# peripherals.net
KiCad netlist of a schematic drawn in Altium Designer
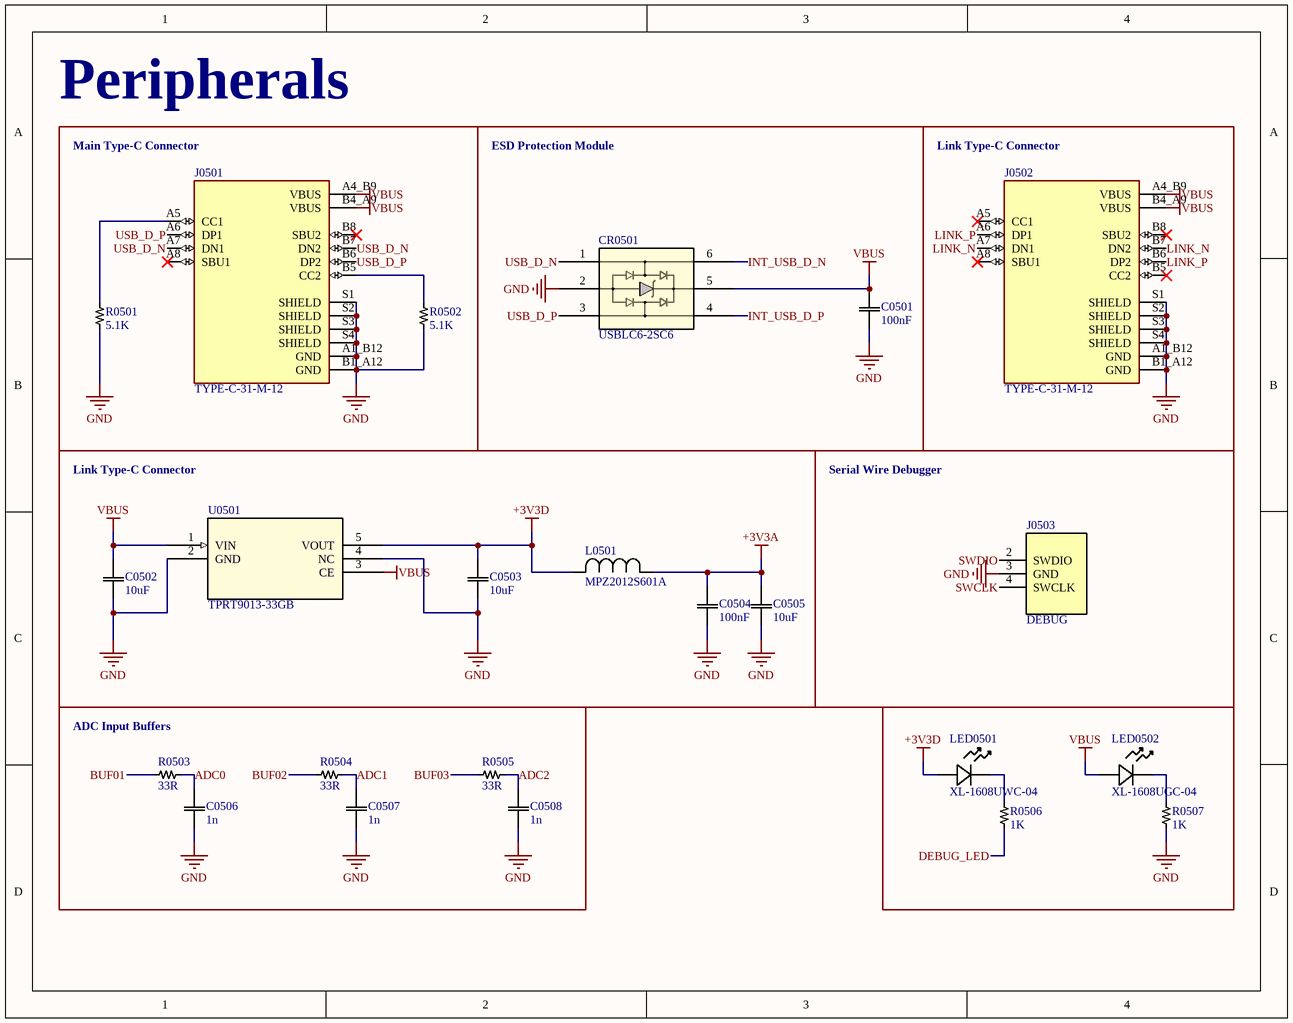
[diagram p0: peripherals.SchDoc]

(export (version "E")
  (design (tool "Eeschema 10.0.6"))
  (components
    (comp (ref "C0501")
      (value "100nF")
      (footprint "CAPC10555_55N_KEM")
      (description "SMD Comm X7R, Ceramic, SMD, MLCC, Temperature Stable, 0402")
      (fields
        (field (name "MANUFACTURER_PART_NUMBER") "C0402C104K4RACTU")
        (field (name "COPYRIGHT") "Copyright (C) 2025 Ultra Librarian. All rights reserved.")
      )
      (libsource (lib "SplitHE_Int") (part "C0402"))
    )
    (comp (ref "C0502")
      (value "10uF")
      (footprint "CAPC10555_55N_KEM")
      (description "SMD Comm X7R, Ceramic, SMD, MLCC, Temperature Stable, 0402")
      (fields
        (field (name "MANUFACTURER_PART_NUMBER") "C0402C104K4RACTU")
        (field (name "COPYRIGHT") "Copyright (C) 2025 Ultra Librarian. All rights reserved.")
      )
      (libsource (lib "SplitHE_Int") (part "C0402"))
    )
    (comp (ref "C0503")
      (value "10uF")
      (footprint "CAPC10555_55N_KEM")
      (description "SMD Comm X7R, Ceramic, SMD, MLCC, Temperature Stable, 0402")
      (fields
        (field (name "MANUFACTURER_PART_NUMBER") "C0402C104K4RACTU")
        (field (name "COPYRIGHT") "Copyright (C) 2025 Ultra Librarian. All rights reserved.")
      )
      (libsource (lib "SplitHE_Int") (part "C0402"))
    )
    (comp (ref "C0504")
      (value "100nF")
      (footprint "CAPC10555_55N_KEM")
      (description "SMD Comm X7R, Ceramic, SMD, MLCC, Temperature Stable, 0402")
      (fields
        (field (name "MANUFACTURER_PART_NUMBER") "C0402C104K4RACTU")
        (field (name "COPYRIGHT") "Copyright (C) 2025 Ultra Librarian. All rights reserved.")
      )
      (libsource (lib "SplitHE_Int") (part "C0402"))
    )
    (comp (ref "C0505")
      (value "10uF")
      (footprint "CAPC10555_55N_KEM")
      (description "SMD Comm X7R, Ceramic, SMD, MLCC, Temperature Stable, 0402")
      (fields
        (field (name "MANUFACTURER_PART_NUMBER") "C0402C104K4RACTU")
        (field (name "COPYRIGHT") "Copyright (C) 2025 Ultra Librarian. All rights reserved.")
      )
      (libsource (lib "SplitHE_Int") (part "C0402"))
    )
    (comp (ref "C0506")
      (value "1n")
      (footprint "CAPC10555_55N_KEM")
      (description "SMD Comm X7R, Ceramic, SMD, MLCC, Temperature Stable, 0402")
      (fields
        (field (name "MANUFACTURER_PART_NUMBER") "C0402C104K4RACTU")
        (field (name "COPYRIGHT") "Copyright (C) 2025 Ultra Librarian. All rights reserved.")
      )
      (libsource (lib "SplitHE_Int") (part "C0402"))
    )
    (comp (ref "C0507")
      (value "1n")
      (footprint "CAPC10555_55N_KEM")
      (description "SMD Comm X7R, Ceramic, SMD, MLCC, Temperature Stable, 0402")
      (fields
        (field (name "MANUFACTURER_PART_NUMBER") "C0402C104K4RACTU")
        (field (name "COPYRIGHT") "Copyright (C) 2025 Ultra Librarian. All rights reserved.")
      )
      (libsource (lib "SplitHE_Int") (part "C0402"))
    )
    (comp (ref "C0508")
      (value "1n")
      (footprint "CAPC10555_55N_KEM")
      (description "SMD Comm X7R, Ceramic, SMD, MLCC, Temperature Stable, 0402")
      (fields
        (field (name "MANUFACTURER_PART_NUMBER") "C0402C104K4RACTU")
        (field (name "COPYRIGHT") "Copyright (C) 2025 Ultra Librarian. All rights reserved.")
      )
      (libsource (lib "SplitHE_Int") (part "C0402"))
    )
    (comp (ref "CR0501")
      (value "USBLC6-2SC6")
      (footprint "SOT23-6L_STM")
      (description "ESD Protection for USB 2.0 High Speed")
      (fields (field (name "COPYRIGHT") "Copyright (C) 2025 Ultra Librarian. All rights reserved."))
      (libsource (lib "SplitHE_Int") (part "USBLC6-2SC6"))
    )
    (comp (ref "J0501")
      (value "TYPE-C-31-M-12")
      (footprint "HRO_TYPE-C-31-M-12")
      (description "USB Connectors 24 Receptacle 1 8.94*7.3mm RoHS")
      (fields (field (name "MF") "HRO Electronics Co., Ltd."))
      (libsource (lib "TYPE-C-31-M-12") (part "TYPE-C-31-M-12"))
    )
    (comp (ref "J0502")
      (value "TYPE-C-31-M-12")
      (footprint "HRO_TYPE-C-31-M-12")
      (description "USB Connectors 24 Receptacle 1 8.94*7.3mm RoHS")
      (fields (field (name "MF") "HRO Electronics Co., Ltd."))
      (libsource (lib "TYPE-C-31-M-12") (part "TYPE-C-31-M-12"))
    )
    (comp (ref "J0503")
      (value "DEBUG")
      (footprint "SW_Debugger_3P")
      (description "Back up plan for serial wire debugging")
      (libsource (lib "SplitHE_Int") (part "DEBUG"))
    )
    (comp (ref "L0501")
      (value "MPZ2012S601A")
      (footprint "IND_MPZ2012_TDK")
      (description "No Description Available")
      (fields (field (name "COPYRIGHT") "Copyright (C) 2025 Ultra Librarian. All rights reserved."))
      (libsource (lib "SplitHE_Int") (part "MPZ2012S601A"))
    )
    (comp (ref "LED0501")
      (value "XL-1608UWC-04")
      (footprint "LED_XL-1608_XLG")
      (description "No Description Available")
      (fields (field (name "COPYRIGHT") "Copyright (C) 2025 Ultra Librarian. All rights reserved."))
      (libsource (lib "SplitHE_Int") (part "XL-1608UWC-04"))
    )
    (comp (ref "LED0502")
      (value "XL-1608UGC-04")
      (footprint "LED_XL-1608_XLG")
      (description "No Description Available")
      (fields
        (field (name "MANUFACTURER_PART_NUMBER") "XL-1608UWC-04")
        (field (name "COPYRIGHT") "Copyright (C) 2025 Ultra Librarian. All rights reserved.")
      )
      (libsource (lib "SplitHE_Int") (part "XL-1608UWC-04"))
    )
    (comp (ref "R0501")
      (value "5.1K")
      (footprint "RES0402_CPF_TYCO_TYC")
      (description "CPF 0402 RL")
      (fields
        (field (name "MANUFACTURER_PART_NUMBER") "CPF0402B33RE1")
        (field (name "COPYRIGHT") "Copyright (C) 2025 Ultra Librarian. All rights reserved.")
      )
      (libsource (lib "SplitHE_Int") (part "R0402"))
    )
    (comp (ref "R0502")
      (value "5.1K")
      (footprint "RES0402_CPF_TYCO_TYC")
      (description "CPF 0402 RL")
      (fields
        (field (name "MANUFACTURER_PART_NUMBER") "CPF0402B33RE1")
        (field (name "COPYRIGHT") "Copyright (C) 2025 Ultra Librarian. All rights reserved.")
      )
      (libsource (lib "SplitHE_Int") (part "R0402"))
    )
    (comp (ref "R0503")
      (value "33R")
      (footprint "RES0402_CPF_TYCO_TYC")
      (description "CPF 0402 RL")
      (fields
        (field (name "MANUFACTURER_PART_NUMBER") "CPF0402B33RE1")
        (field (name "COPYRIGHT") "Copyright (C) 2025 Ultra Librarian. All rights reserved.")
      )
      (libsource (lib "SplitHE_Int") (part "R0402"))
    )
    (comp (ref "R0504")
      (value "33R")
      (footprint "RES0402_CPF_TYCO_TYC")
      (description "CPF 0402 RL")
      (fields
        (field (name "MANUFACTURER_PART_NUMBER") "CPF0402B33RE1")
        (field (name "COPYRIGHT") "Copyright (C) 2025 Ultra Librarian. All rights reserved.")
      )
      (libsource (lib "SplitHE_Int") (part "R0402"))
    )
    (comp (ref "R0505")
      (value "33R")
      (footprint "RES0402_CPF_TYCO_TYC")
      (description "CPF 0402 RL")
      (fields
        (field (name "MANUFACTURER_PART_NUMBER") "CPF0402B33RE1")
        (field (name "COPYRIGHT") "Copyright (C) 2025 Ultra Librarian. All rights reserved.")
      )
      (libsource (lib "SplitHE_Int") (part "R0402"))
    )
    (comp (ref "R0506")
      (value "1K")
      (footprint "RES0402_CPF_TYCO_TYC")
      (description "CPF 0402 RL")
      (fields
        (field (name "MANUFACTURER_PART_NUMBER") "CPF0402B33RE1")
        (field (name "COPYRIGHT") "Copyright (C) 2025 Ultra Librarian. All rights reserved.")
      )
      (libsource (lib "SplitHE_Int") (part "R0402"))
    )
    (comp (ref "R0507")
      (value "1K")
      (footprint "RES0402_CPF_TYCO_TYC")
      (description "CPF 0402 RL")
      (fields
        (field (name "MANUFACTURER_PART_NUMBER") "CPF0402B33RE1")
        (field (name "COPYRIGHT") "Copyright (C) 2025 Ultra Librarian. All rights reserved.")
      )
      (libsource (lib "SplitHE_Int") (part "R0402"))
    )
    (comp (ref "U0501")
      (value "TPRT9013-33GB")
      (footprint "SOT23-5_TCP")
      (description "No Description Available")
      (fields (field (name "COPYRIGHT") "Copyright (C) 2025 Ultra Librarian. All rights reserved."))
      (libsource (lib "SplitHE_Int") (part "TPRT9013-33GB"))
    )
  )
  (nets
    (net (code "1") (name "+3V3A") (class "Default")
      (node (ref "C0504") (pin "2") (pinfunction "2_2") (pintype "passive"))
      (node (ref "C0505") (pin "2") (pinfunction "2_2") (pintype "passive"))
      (node (ref "L0501") (pin "1") (pinfunction "1_1") (pintype "passive"))
    )
    (net (code "2") (name "+3V3D") (class "Default")
      (node (ref "C0503") (pin "2") (pinfunction "2_2") (pintype "passive"))
      (node (ref "L0501") (pin "2") (pinfunction "2_2") (pintype "passive"))
      (node (ref "LED0501") (pin "2") (pinfunction "ANODE_2") (pintype "passive"))
      (node (ref "U0501") (pin "5") (pinfunction "VOUT_5") (pintype "power_in"))
    )
    (net (code "3") (name "/ADC0") (class "Default")
      (node (ref "C0506") (pin "2") (pinfunction "2_2") (pintype "passive"))
      (node (ref "R0503") (pin "1") (pinfunction "1_1") (pintype "passive"))
    )
    (net (code "4") (name "/ADC1") (class "Default")
      (node (ref "C0507") (pin "2") (pinfunction "2_2") (pintype "passive"))
      (node (ref "R0504") (pin "1") (pinfunction "1_1") (pintype "passive"))
    )
    (net (code "5") (name "/ADC2") (class "Default")
      (node (ref "C0508") (pin "2") (pinfunction "2_2") (pintype "passive"))
      (node (ref "R0505") (pin "1") (pinfunction "1_1") (pintype "passive"))
    )
    (net (code "6") (name "/BUF01") (class "Default")
      (node (ref "R0503") (pin "2") (pinfunction "2_2") (pintype "passive"))
    )
    (net (code "7") (name "/BUF02") (class "Default")
      (node (ref "R0504") (pin "2") (pinfunction "2_2") (pintype "passive"))
    )
    (net (code "8") (name "/BUF03") (class "Default")
      (node (ref "R0505") (pin "2") (pinfunction "2_2") (pintype "passive"))
    )
    (net (code "9") (name "/DEBUG_LED") (class "Default")
      (node (ref "R0506") (pin "2") (pinfunction "2_2") (pintype "passive"))
    )
    (net (code "10") (name "/INT_USB_D_N") (class "Default")
      (node (ref "CR0501") (pin "6") (pinfunction "6_6") (pintype "passive"))
    )
    (net (code "11") (name "/INT_USB_D_P") (class "Default")
      (node (ref "CR0501") (pin "4") (pinfunction "4_4") (pintype "passive"))
    )
    (net (code "12") (name "/LINK_N") (class "Default")
      (node (ref "J0502") (pin "A7") (pinfunction "DN1_A7") (pintype "bidirectional"))
      (node (ref "J0502") (pin "B7") (pinfunction "DN2_B7") (pintype "bidirectional"))
    )
    (net (code "13") (name "/LINK_P") (class "Default")
      (node (ref "J0502") (pin "A6") (pinfunction "DP1_A6") (pintype "bidirectional"))
      (node (ref "J0502") (pin "B6") (pinfunction "DP2_B6") (pintype "bidirectional"))
    )
    (net (code "14") (name "/SWCLK") (class "Default")
      (node (ref "J0503") (pin "4") (pinfunction "SWCLK_4") (pintype "passive"))
    )
    (net (code "15") (name "/SWDIO") (class "Default")
      (node (ref "J0503") (pin "2") (pinfunction "SWDIO_2") (pintype "passive"))
    )
    (net (code "16") (name "/USB_D_N") (class "Default")
      (node (ref "CR0501") (pin "1") (pinfunction "1_1") (pintype "passive"))
      (node (ref "J0501") (pin "A7") (pinfunction "DN1_A7") (pintype "bidirectional"))
      (node (ref "J0501") (pin "B7") (pinfunction "DN2_B7") (pintype "bidirectional"))
    )
    (net (code "17") (name "/USB_D_P") (class "Default")
      (node (ref "CR0501") (pin "3") (pinfunction "3_3") (pintype "passive"))
      (node (ref "J0501") (pin "A6") (pinfunction "DP1_A6") (pintype "bidirectional"))
      (node (ref "J0501") (pin "B6") (pinfunction "DP2_B6") (pintype "bidirectional"))
    )
    (net (code "18") (name "GND") (class "Default")
      (node (ref "C0501") (pin "1") (pinfunction "1_1") (pintype "passive"))
      (node (ref "C0502") (pin "1") (pinfunction "1_1") (pintype "passive"))
      (node (ref "C0503") (pin "1") (pinfunction "1_1") (pintype "passive"))
      (node (ref "C0504") (pin "1") (pinfunction "1_1") (pintype "passive"))
      (node (ref "C0505") (pin "1") (pinfunction "1_1") (pintype "passive"))
      (node (ref "C0506") (pin "1") (pinfunction "1_1") (pintype "passive"))
      (node (ref "C0507") (pin "1") (pinfunction "1_1") (pintype "passive"))
      (node (ref "C0508") (pin "1") (pinfunction "1_1") (pintype "passive"))
      (node (ref "CR0501") (pin "2") (pinfunction "2_2") (pintype "passive"))
      (node (ref "J0501") (pin "A1_B12") (pinfunction "GND_A1_B12") (pintype "power_in"))
      (node (ref "J0501") (pin "B1_A12") (pinfunction "GND_B1_A12") (pintype "power_in"))
      (node (ref "J0501") (pin "S1") (pinfunction "SHIELD_S1") (pintype "passive"))
      (node (ref "J0501") (pin "S2") (pinfunction "SHIELD_S2") (pintype "passive"))
      (node (ref "J0501") (pin "S3") (pinfunction "SHIELD_S3") (pintype "passive"))
      (node (ref "J0501") (pin "S4") (pinfunction "SHIELD_S4") (pintype "passive"))
      (node (ref "J0502") (pin "A1_B12") (pinfunction "GND_A1_B12") (pintype "power_in"))
      (node (ref "J0502") (pin "B1_A12") (pinfunction "GND_B1_A12") (pintype "power_in"))
      (node (ref "J0502") (pin "S1") (pinfunction "SHIELD_S1") (pintype "passive"))
      (node (ref "J0502") (pin "S2") (pinfunction "SHIELD_S2") (pintype "passive"))
      (node (ref "J0502") (pin "S3") (pinfunction "SHIELD_S3") (pintype "passive"))
      (node (ref "J0502") (pin "S4") (pinfunction "SHIELD_S4") (pintype "passive"))
      (node (ref "J0503") (pin "3") (pinfunction "GND_3") (pintype "passive"))
      (node (ref "R0501") (pin "1") (pinfunction "1_1") (pintype "passive"))
      (node (ref "R0502") (pin "1") (pinfunction "1_1") (pintype "passive"))
      (node (ref "R0507") (pin "2") (pinfunction "2_2") (pintype "passive"))
      (node (ref "U0501") (pin "2") (pinfunction "GND_2") (pintype "power_in"))
      (node (ref "U0501") (pin "4") (pinfunction "NC_4") (pintype "passive"))
    )
    (net (code "19") (name "Net-(J0501-CC1)") (class "Default")
      (node (ref "J0501") (pin "A5") (pinfunction "CC1_A5") (pintype "bidirectional"))
      (node (ref "R0501") (pin "2") (pinfunction "2_2") (pintype "passive"))
    )
    (net (code "20") (name "Net-(J0501-CC2)") (class "Default")
      (node (ref "J0501") (pin "B5") (pinfunction "CC2_B5") (pintype "bidirectional"))
      (node (ref "R0502") (pin "2") (pinfunction "2_2") (pintype "passive"))
    )
    (net (code "21") (name "Net-(LED0501-CATHODE)") (class "Default")
      (node (ref "LED0501") (pin "1") (pinfunction "CATHODE_1") (pintype "passive"))
      (node (ref "R0506") (pin "1") (pinfunction "1_1") (pintype "passive"))
    )
    (net (code "22") (name "Net-(LED0502-CATHODE)") (class "Default")
      (node (ref "LED0502") (pin "1") (pinfunction "CATHODE_1") (pintype "passive"))
      (node (ref "R0507") (pin "1") (pinfunction "1_1") (pintype "passive"))
    )
    (net (code "23") (name "VBUS") (class "Default")
      (node (ref "C0501") (pin "2") (pinfunction "2_2") (pintype "passive"))
      (node (ref "C0502") (pin "2") (pinfunction "2_2") (pintype "passive"))
      (node (ref "CR0501") (pin "5") (pinfunction "5_5") (pintype "passive"))
      (node (ref "J0501") (pin "A4_B9") (pinfunction "VBUS_A4_B9") (pintype "power_in"))
      (node (ref "J0501") (pin "B4_A9") (pinfunction "VBUS_B4_A9") (pintype "power_in"))
      (node (ref "J0502") (pin "A4_B9") (pinfunction "VBUS_A4_B9") (pintype "power_in"))
      (node (ref "J0502") (pin "B4_A9") (pinfunction "VBUS_B4_A9") (pintype "power_in"))
      (node (ref "LED0502") (pin "2") (pinfunction "ANODE_2") (pintype "passive"))
      (node (ref "U0501") (pin "1") (pinfunction "VIN_1") (pintype "input"))
      (node (ref "U0501") (pin "3") (pinfunction "CE_3") (pintype "passive"))
    )
    (net (code "24") (name "unconnected-(J0501-SBU1-PadA8)") (class "Default")
      (node (ref "J0501") (pin "A8") (pinfunction "SBU1_A8") (pintype "bidirectional+no_connect"))
    )
    (net (code "25") (name "unconnected-(J0501-SBU2-PadB8)") (class "Default")
      (node (ref "J0501") (pin "B8") (pinfunction "SBU2_B8") (pintype "bidirectional+no_connect"))
    )
    (net (code "26") (name "unconnected-(J0502-CC1-PadA5)") (class "Default")
      (node (ref "J0502") (pin "A5") (pinfunction "CC1_A5") (pintype "bidirectional+no_connect"))
    )
    (net (code "27") (name "unconnected-(J0502-CC2-PadB5)") (class "Default")
      (node (ref "J0502") (pin "B5") (pinfunction "CC2_B5") (pintype "bidirectional+no_connect"))
    )
    (net (code "28") (name "unconnected-(J0502-SBU1-PadA8)") (class "Default")
      (node (ref "J0502") (pin "A8") (pinfunction "SBU1_A8") (pintype "bidirectional+no_connect"))
    )
    (net (code "29") (name "unconnected-(J0502-SBU2-PadB8)") (class "Default")
      (node (ref "J0502") (pin "B8") (pinfunction "SBU2_B8") (pintype "bidirectional+no_connect"))
    )
  )
)
